# mp3playerLabor_v1.net
KiCad netlist of a schematic drawn in EAGLE
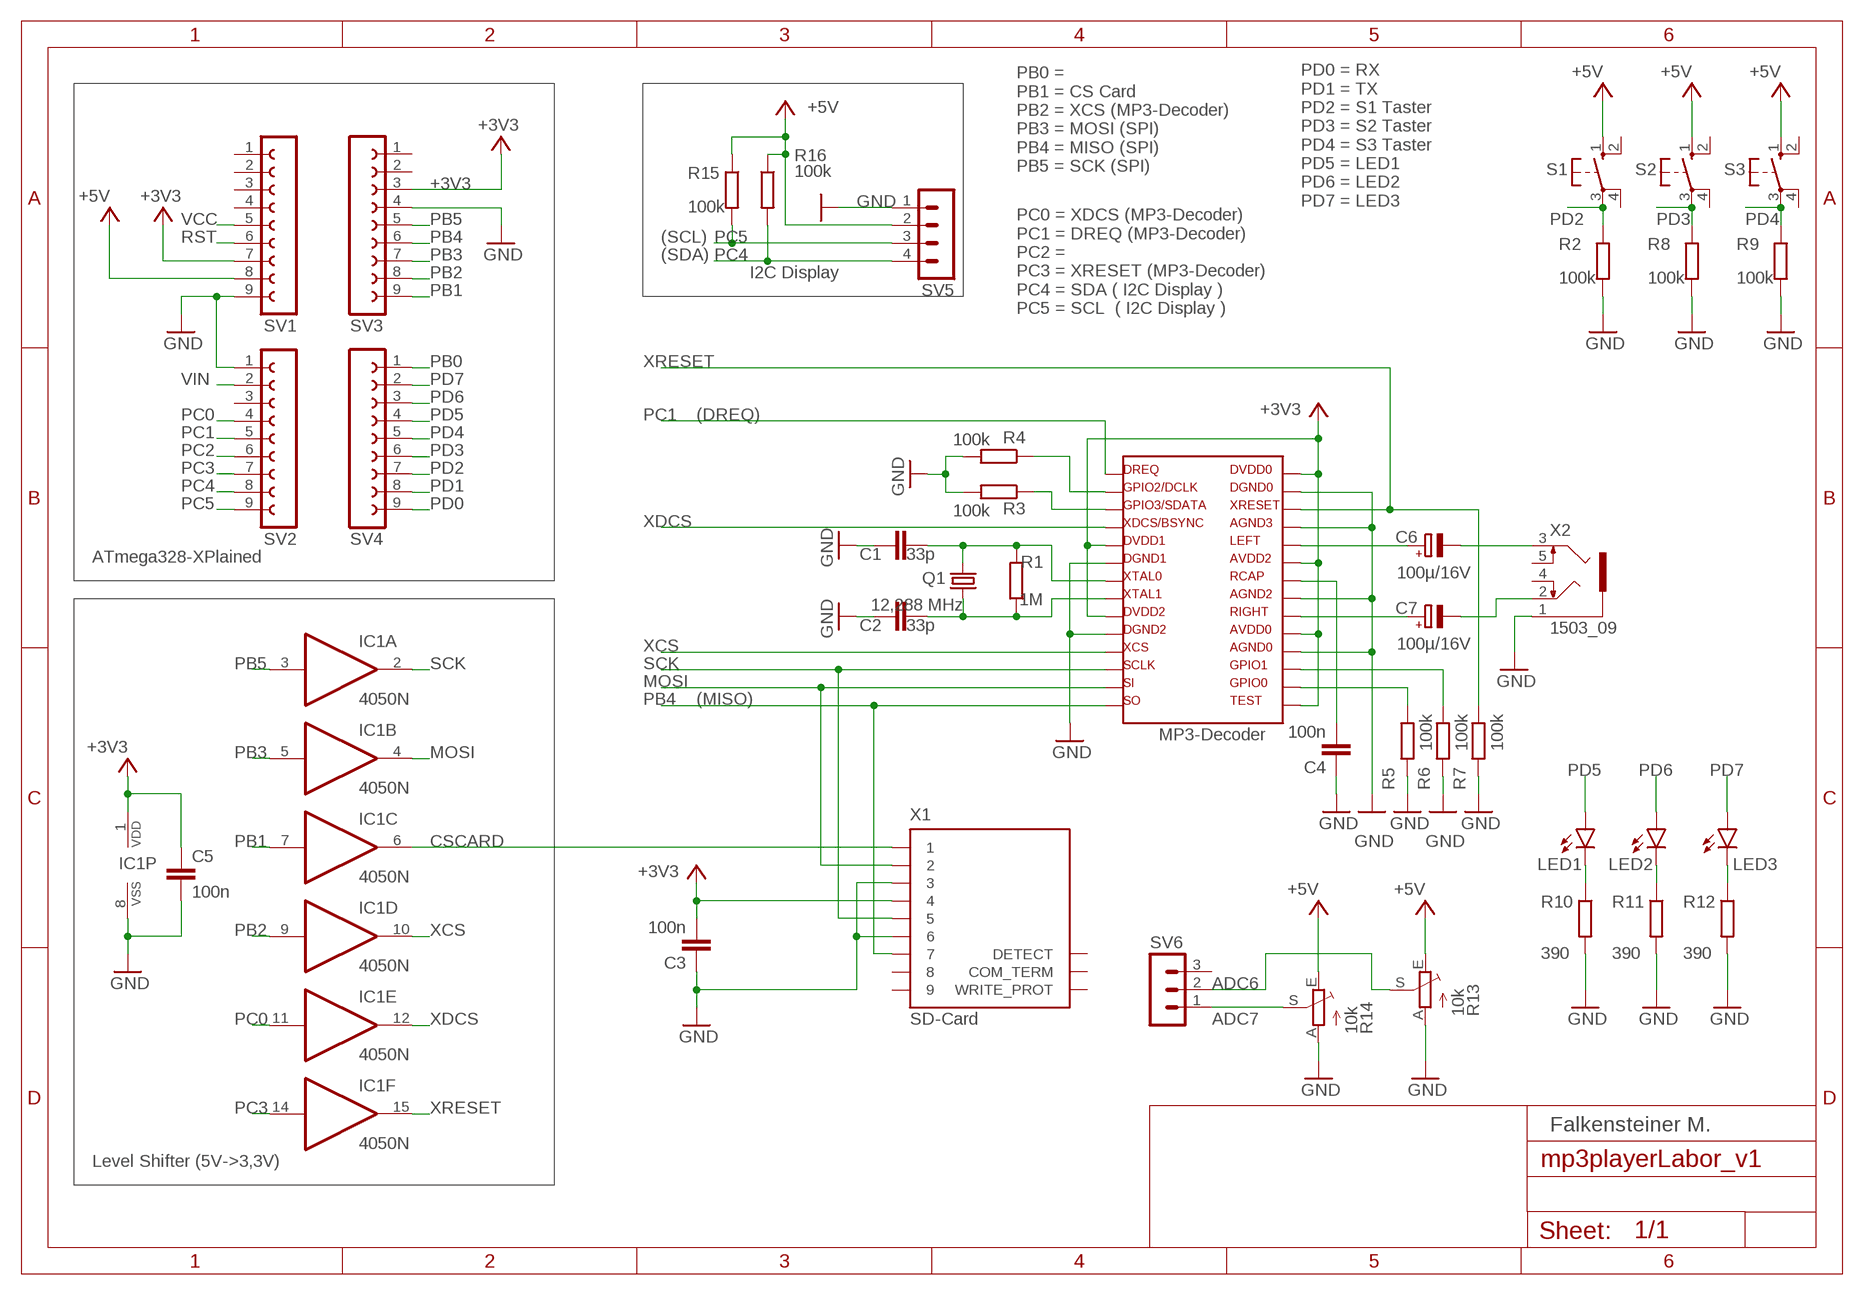
[diagram p0: schematic, sheet 1]

(export (version "E")
  (design (tool "Eeschema 10.0.6"))
  (components
    (comp (ref "C1")
      (value "33p")
      (footprint "eagle-import:C1206K")
      (libsource (lib "eagle-import") (part "C-EUC1206K"))
    )
    (comp (ref "C2")
      (value "33p")
      (footprint "eagle-import:C1206K")
      (libsource (lib "eagle-import") (part "C-EUC1206K"))
    )
    (comp (ref "C3")
      (value "100n")
      (footprint "eagle-import:C1206K")
      (libsource (lib "eagle-import") (part "C-EUC1206K"))
    )
    (comp (ref "C4")
      (value "100n")
      (footprint "eagle-import:C1206K")
      (libsource (lib "eagle-import") (part "C-EUC1206K"))
    )
    (comp (ref "C5")
      (value "100n")
      (footprint "eagle-import:C1206K")
      (libsource (lib "eagle-import") (part "C-EUC1206K"))
    )
    (comp (ref "C6")
      (value "100µ/16V")
      (footprint "eagle-import:UD-6,3X7,7_NICHICON")
      (libsource (lib "eagle-import") (part "CPOL-EUUD-6,3X7,7"))
    )
    (comp (ref "C7")
      (value "100µ/16V")
      (footprint "eagle-import:UD-6,3X7,7_NICHICON")
      (libsource (lib "eagle-import") (part "CPOL-EUUD-6,3X7,7"))
    )
    (comp (ref "IC1")
      (value "4050N")
      (footprint "eagle-import:DIL16")
      (libsource (lib "eagle-import") (part "4050N"))
    )
    (comp (ref "LED1")
      (value "LEDSML1206")
      (footprint "eagle-import:SML1206")
      (libsource (lib "eagle-import") (part "LEDSML1206"))
    )
    (comp (ref "LED2")
      (value "LEDSML1206")
      (footprint "eagle-import:SML1206")
      (libsource (lib "eagle-import") (part "LEDSML1206"))
    )
    (comp (ref "LED3")
      (value "LEDSML1206")
      (footprint "eagle-import:SML1206")
      (libsource (lib "eagle-import") (part "LEDSML1206"))
    )
    (comp (ref "Q1")
      (value "12,288 MHz")
      (footprint "eagle-import:HC49UP")
      (libsource (lib "eagle-import") (part "CRYSTALHC49UP"))
    )
    (comp (ref "R1")
      (value "1M")
      (footprint "eagle-import:R1206")
      (libsource (lib "eagle-import") (part "R-EU_R1206"))
    )
    (comp (ref "R2")
      (value "100k")
      (footprint "eagle-import:R1206")
      (libsource (lib "eagle-import") (part "R-EU_R1206"))
    )
    (comp (ref "R3")
      (value "100k")
      (footprint "eagle-import:R1206")
      (libsource (lib "eagle-import") (part "R-EU_R1206"))
    )
    (comp (ref "R4")
      (value "100k")
      (footprint "eagle-import:R1206")
      (libsource (lib "eagle-import") (part "R-EU_R1206"))
    )
    (comp (ref "R5")
      (value "100k")
      (footprint "eagle-import:R1206")
      (libsource (lib "eagle-import") (part "R-EU_R1206"))
    )
    (comp (ref "R6")
      (value "100k")
      (footprint "eagle-import:R1206")
      (libsource (lib "eagle-import") (part "R-EU_R1206"))
    )
    (comp (ref "R7")
      (value "100k")
      (footprint "eagle-import:R1206")
      (libsource (lib "eagle-import") (part "R-EU_R1206"))
    )
    (comp (ref "R8")
      (value "100k")
      (footprint "eagle-import:R1206")
      (libsource (lib "eagle-import") (part "R-EU_R1206"))
    )
    (comp (ref "R9")
      (value "100k")
      (footprint "eagle-import:R1206")
      (libsource (lib "eagle-import") (part "R-EU_R1206"))
    )
    (comp (ref "R10")
      (value "390")
      (footprint "eagle-import:R1206")
      (libsource (lib "eagle-import") (part "R-EU_R1206"))
    )
    (comp (ref "R11")
      (value "390")
      (footprint "eagle-import:R1206")
      (libsource (lib "eagle-import") (part "R-EU_R1206"))
    )
    (comp (ref "R12")
      (value "390")
      (footprint "eagle-import:R1206")
      (libsource (lib "eagle-import") (part "R-EU_R1206"))
    )
    (comp (ref "R13")
      (value "10k")
      (footprint "eagle-import:CA6V")
      (libsource (lib "eagle-import") (part "TRIM_EU-CA6V"))
    )
    (comp (ref "R14")
      (value "10k")
      (footprint "eagle-import:CA6V")
      (libsource (lib "eagle-import") (part "TRIM_EU-CA6V"))
    )
    (comp (ref "R15")
      (value "100k")
      (footprint "eagle-import:R1206")
      (libsource (lib "eagle-import") (part "R-EU_R1206"))
    )
    (comp (ref "R16")
      (value "100k")
      (footprint "eagle-import:R1206")
      (libsource (lib "eagle-import") (part "R-EU_R1206"))
    )
    (comp (ref "S1")
      (value "10-XX")
      (footprint "eagle-import:B3F-10XX")
      (libsource (lib "eagle-import") (part "10-XX"))
    )
    (comp (ref "S2")
      (value "10-XX")
      (footprint "eagle-import:B3F-10XX")
      (libsource (lib "eagle-import") (part "10-XX"))
    )
    (comp (ref "S3")
      (value "10-XX")
      (footprint "eagle-import:B3F-10XX")
      (libsource (lib "eagle-import") (part "10-XX"))
    )
    (comp (ref "SV1")
      (value "FE09-1")
      (footprint "eagle-import:FE09")
      (libsource (lib "eagle-import") (part "FE09-1"))
    )
    (comp (ref "SV2")
      (value "FE09-1")
      (footprint "eagle-import:FE09")
      (libsource (lib "eagle-import") (part "FE09-1"))
    )
    (comp (ref "SV3")
      (value "FE09-1")
      (footprint "eagle-import:FE09")
      (libsource (lib "eagle-import") (part "FE09-1"))
    )
    (comp (ref "SV4")
      (value "FE09-1")
      (footprint "eagle-import:FE09")
      (libsource (lib "eagle-import") (part "FE09-1"))
    )
    (comp (ref "SV5")
      (value "MA04-1")
      (footprint "eagle-import:MA04-1")
      (libsource (lib "eagle-import") (part "MA04-1"))
    )
    (comp (ref "SV6")
      (value "MA03-1")
      (footprint "eagle-import:MA03-1")
      (libsource (lib "eagle-import") (part "MA03-1"))
    )
    (comp (ref "U$1")
      (value "VS1011")
      (footprint "eagle-import:SOIC-28")
      (libsource (lib "eagle-import") (part "VS1011"))
    )
    (comp (ref "X1")
      (value "SD-Card")
      (footprint "eagle-import:FPS009-3000")
      (libsource (lib "eagle-import") (part "FPS009-3000"))
    )
    (comp (ref "X2")
      (value "1503_09")
      (footprint "eagle-import:1503_09")
      (libsource (lib "eagle-import") (part "1503_09"))
    )
  )
  (nets
    (net (code "1") (name "+3V3") (class "Default")
      (node (ref "C3") (pin "2") (pinfunction "2_2") (pintype "passive"))
      (node (ref "C5") (pin "1") (pinfunction "1_1") (pintype "passive"))
      (node (ref "IC1") (pin "1") (pinfunction "VDD_1") (pintype "power_in"))
      (node (ref "SV1") (pin "7") (pinfunction "7_7") (pintype "passive"))
      (node (ref "SV3") (pin "3") (pinfunction "3_3") (pintype "passive"))
      (node (ref "U$1") (pin "15") (pinfunction "P$15_15") (pintype "bidirectional"))
      (node (ref "U$1") (pin "19") (pinfunction "P$19_19") (pintype "bidirectional"))
      (node (ref "U$1") (pin "23") (pinfunction "P$23_23") (pintype "bidirectional"))
      (node (ref "U$1") (pin "28") (pinfunction "P$28_28") (pintype "bidirectional"))
      (node (ref "U$1") (pin "5") (pinfunction "P$5_5") (pintype "bidirectional"))
      (node (ref "U$1") (pin "9") (pinfunction "P$9_9") (pintype "bidirectional"))
      (node (ref "X1") (pin "4") (pinfunction "4_4") (pintype "input"))
    )
    (net (code "2") (name "+5V") (class "Default")
      (node (ref "R13") (pin "E") (pinfunction "E_E") (pintype "passive"))
      (node (ref "R14") (pin "E") (pinfunction "E_E") (pintype "passive"))
      (node (ref "R15") (pin "1") (pinfunction "1_1") (pintype "passive"))
      (node (ref "R16") (pin "1") (pinfunction "1_1") (pintype "passive"))
      (node (ref "S1") (pin "1") (pinfunction "S_1") (pintype "passive"))
      (node (ref "S2") (pin "1") (pinfunction "S_1") (pintype "passive"))
      (node (ref "S3") (pin "1") (pinfunction "S_1") (pintype "passive"))
      (node (ref "SV1") (pin "8") (pinfunction "8_8") (pintype "passive"))
      (node (ref "SV5") (pin "2") (pinfunction "2_2") (pintype "passive"))
    )
    (net (code "3") (name "/ADC6") (class "Default")
      (node (ref "R13") (pin "S") (pinfunction "S_S") (pintype "passive"))
      (node (ref "SV6") (pin "2") (pinfunction "2_2") (pintype "passive"))
    )
    (net (code "4") (name "/ADC7") (class "Default")
      (node (ref "R14") (pin "S") (pinfunction "S_S") (pintype "passive"))
      (node (ref "SV6") (pin "1") (pinfunction "1_1") (pintype "passive"))
    )
    (net (code "5") (name "/CSCARD") (class "Default")
      (node (ref "IC1") (pin "6") (pinfunction "O_6") (pintype "output"))
      (node (ref "X1") (pin "1") (pinfunction "1_1") (pintype "input"))
    )
    (net (code "6") (name "/MOSI") (class "Default")
      (node (ref "IC1") (pin "4") (pinfunction "O_4") (pintype "output"))
      (node (ref "U$1") (pin "13") (pinfunction "P$13_13") (pintype "bidirectional"))
      (node (ref "X1") (pin "2") (pinfunction "2_2") (pintype "input"))
    )
    (net (code "7") (name "/PB0") (class "Default")
      (node (ref "SV4") (pin "1") (pinfunction "1_1") (pintype "passive"))
    )
    (net (code "8") (name "/PB1") (class "Default")
      (node (ref "IC1") (pin "7") (pinfunction "I_7") (pintype "input"))
      (node (ref "SV3") (pin "9") (pinfunction "9_9") (pintype "passive"))
    )
    (net (code "9") (name "/PB2") (class "Default")
      (node (ref "IC1") (pin "9") (pinfunction "I_9") (pintype "input"))
      (node (ref "SV3") (pin "8") (pinfunction "8_8") (pintype "passive"))
    )
    (net (code "10") (name "/PB3") (class "Default")
      (node (ref "IC1") (pin "5") (pinfunction "I_5") (pintype "input"))
      (node (ref "SV3") (pin "7") (pinfunction "7_7") (pintype "passive"))
    )
    (net (code "11") (name "/PB4") (class "Default")
      (node (ref "SV3") (pin "6") (pinfunction "6_6") (pintype "passive"))
      (node (ref "U$1") (pin "14") (pinfunction "P$14_14") (pintype "bidirectional"))
      (node (ref "X1") (pin "7") (pinfunction "7_7") (pintype "input"))
    )
    (net (code "12") (name "/PB5") (class "Default")
      (node (ref "IC1") (pin "3") (pinfunction "I_3") (pintype "input"))
      (node (ref "SV3") (pin "5") (pinfunction "5_5") (pintype "passive"))
    )
    (net (code "13") (name "/PC0") (class "Default")
      (node (ref "IC1") (pin "11") (pinfunction "I_11") (pintype "input"))
      (node (ref "SV2") (pin "4") (pinfunction "4_4") (pintype "passive"))
    )
    (net (code "14") (name "/PC1") (class "Default")
      (node (ref "SV2") (pin "5") (pinfunction "5_5") (pintype "passive"))
      (node (ref "U$1") (pin "1") (pinfunction "P$1_1") (pintype "bidirectional"))
    )
    (net (code "15") (name "/PC2") (class "Default")
      (node (ref "SV2") (pin "6") (pinfunction "6_6") (pintype "passive"))
    )
    (net (code "16") (name "/PC3") (class "Default")
      (node (ref "IC1") (pin "14") (pinfunction "I_14") (pintype "input"))
      (node (ref "SV2") (pin "7") (pinfunction "7_7") (pintype "passive"))
    )
    (net (code "17") (name "/PC4") (class "Default")
      (node (ref "R16") (pin "2") (pinfunction "2_2") (pintype "passive"))
      (node (ref "SV2") (pin "8") (pinfunction "8_8") (pintype "passive"))
      (node (ref "SV5") (pin "4") (pinfunction "4_4") (pintype "passive"))
    )
    (net (code "18") (name "/PC5") (class "Default")
      (node (ref "R15") (pin "2") (pinfunction "2_2") (pintype "passive"))
      (node (ref "SV2") (pin "9") (pinfunction "9_9") (pintype "passive"))
      (node (ref "SV5") (pin "3") (pinfunction "3_3") (pintype "passive"))
    )
    (net (code "19") (name "/PD0") (class "Default")
      (node (ref "SV4") (pin "9") (pinfunction "9_9") (pintype "passive"))
    )
    (net (code "20") (name "/PD1") (class "Default")
      (node (ref "SV4") (pin "8") (pinfunction "8_8") (pintype "passive"))
    )
    (net (code "21") (name "/PD2") (class "Default")
      (node (ref "R2") (pin "1") (pinfunction "1_1") (pintype "passive"))
      (node (ref "S1") (pin "3") (pinfunction "P_3") (pintype "passive"))
      (node (ref "SV4") (pin "7") (pinfunction "7_7") (pintype "passive"))
    )
    (net (code "22") (name "/PD3") (class "Default")
      (node (ref "R8") (pin "1") (pinfunction "1_1") (pintype "passive"))
      (node (ref "S2") (pin "3") (pinfunction "P_3") (pintype "passive"))
      (node (ref "SV4") (pin "6") (pinfunction "6_6") (pintype "passive"))
    )
    (net (code "23") (name "/PD4") (class "Default")
      (node (ref "R9") (pin "1") (pinfunction "1_1") (pintype "passive"))
      (node (ref "S3") (pin "3") (pinfunction "P_3") (pintype "passive"))
      (node (ref "SV4") (pin "5") (pinfunction "5_5") (pintype "passive"))
    )
    (net (code "24") (name "/PD5") (class "Default")
      (node (ref "LED1") (pin "A") (pinfunction "A_A") (pintype "passive"))
      (node (ref "SV4") (pin "4") (pinfunction "4_4") (pintype "passive"))
    )
    (net (code "25") (name "/PD6") (class "Default")
      (node (ref "LED2") (pin "A") (pinfunction "A_A") (pintype "passive"))
      (node (ref "SV4") (pin "3") (pinfunction "3_3") (pintype "passive"))
    )
    (net (code "26") (name "/PD7") (class "Default")
      (node (ref "LED3") (pin "A") (pinfunction "A_A") (pintype "passive"))
      (node (ref "SV4") (pin "2") (pinfunction "2_2") (pintype "passive"))
    )
    (net (code "27") (name "/RST") (class "Default")
      (node (ref "SV1") (pin "6") (pinfunction "6_6") (pintype "passive"))
    )
    (net (code "28") (name "/SCK") (class "Default")
      (node (ref "IC1") (pin "2") (pinfunction "O_2") (pintype "output"))
      (node (ref "U$1") (pin "12") (pinfunction "P$12_12") (pintype "bidirectional"))
      (node (ref "X1") (pin "5") (pinfunction "5_5") (pintype "input"))
    )
    (net (code "29") (name "/VCC") (class "Default")
      (node (ref "SV1") (pin "5") (pinfunction "5_5") (pintype "passive"))
    )
    (net (code "30") (name "/VIN") (class "Default")
      (node (ref "SV2") (pin "2") (pinfunction "2_2") (pintype "passive"))
    )
    (net (code "31") (name "/XCS") (class "Default")
      (node (ref "IC1") (pin "10") (pinfunction "O_10") (pintype "output"))
      (node (ref "U$1") (pin "11") (pinfunction "P$11_11") (pintype "bidirectional"))
    )
    (net (code "32") (name "/XDCS") (class "Default")
      (node (ref "IC1") (pin "12") (pinfunction "O_12") (pintype "output"))
      (node (ref "U$1") (pin "4") (pinfunction "P$4_4") (pintype "bidirectional"))
    )
    (net (code "33") (name "/XRESET") (class "Default")
      (node (ref "IC1") (pin "15") (pinfunction "O_15") (pintype "output"))
      (node (ref "R7") (pin "1") (pinfunction "1_1") (pintype "passive"))
      (node (ref "U$1") (pin "26") (pinfunction "P$26_26") (pintype "bidirectional"))
    )
    (net (code "34") (name "GND") (class "Default")
      (node (ref "C1") (pin "1") (pinfunction "1_1") (pintype "passive"))
      (node (ref "C2") (pin "1") (pinfunction "1_1") (pintype "passive"))
      (node (ref "C3") (pin "1") (pinfunction "1_1") (pintype "passive"))
      (node (ref "C4") (pin "1") (pinfunction "1_1") (pintype "passive"))
      (node (ref "C5") (pin "2") (pinfunction "2_2") (pintype "passive"))
      (node (ref "IC1") (pin "8") (pinfunction "VSS_8") (pintype "power_in"))
      (node (ref "R10") (pin "2") (pinfunction "2_2") (pintype "passive"))
      (node (ref "R11") (pin "2") (pinfunction "2_2") (pintype "passive"))
      (node (ref "R12") (pin "2") (pinfunction "2_2") (pintype "passive"))
      (node (ref "R13") (pin "A") (pinfunction "A_A") (pintype "passive"))
      (node (ref "R14") (pin "A") (pinfunction "A_A") (pintype "passive"))
      (node (ref "R2") (pin "2") (pinfunction "2_2") (pintype "passive"))
      (node (ref "R3") (pin "2") (pinfunction "2_2") (pintype "passive"))
      (node (ref "R4") (pin "2") (pinfunction "2_2") (pintype "passive"))
      (node (ref "R5") (pin "2") (pinfunction "2_2") (pintype "passive"))
      (node (ref "R6") (pin "2") (pinfunction "2_2") (pintype "passive"))
      (node (ref "R7") (pin "2") (pinfunction "2_2") (pintype "passive"))
      (node (ref "R8") (pin "2") (pinfunction "2_2") (pintype "passive"))
      (node (ref "R9") (pin "2") (pinfunction "2_2") (pintype "passive"))
      (node (ref "SV1") (pin "9") (pinfunction "9_9") (pintype "passive"))
      (node (ref "SV2") (pin "1") (pinfunction "1_1") (pintype "passive"))
      (node (ref "SV3") (pin "4") (pinfunction "4_4") (pintype "passive"))
      (node (ref "SV5") (pin "1") (pinfunction "1_1") (pintype "passive"))
      (node (ref "U$1") (pin "10") (pinfunction "P$10_10") (pintype "bidirectional"))
      (node (ref "U$1") (pin "18") (pinfunction "P$18_18") (pintype "bidirectional"))
      (node (ref "U$1") (pin "21") (pinfunction "P$21_21") (pintype "bidirectional"))
      (node (ref "U$1") (pin "25") (pinfunction "P$25_25") (pintype "bidirectional"))
      (node (ref "U$1") (pin "27") (pinfunction "P$27_27") (pintype "bidirectional"))
      (node (ref "U$1") (pin "6") (pinfunction "P$6_6") (pintype "bidirectional"))
      (node (ref "X1") (pin "3") (pinfunction "3_3") (pintype "input"))
      (node (ref "X1") (pin "6") (pinfunction "6_6") (pintype "input"))
      (node (ref "X2") (pin "1") (pinfunction "1_1") (pintype "passive"))
    )
    (net (code "35") (name "Net-(C6-Pad-)") (class "Default")
      (node (ref "C6") (pin "-") (pinfunction "-_-") (pintype "passive"))
      (node (ref "X2") (pin "3") (pinfunction "3_3") (pintype "passive"))
    )
    (net (code "36") (name "Net-(C7-Pad-)") (class "Default")
      (node (ref "C7") (pin "-") (pinfunction "-_-") (pintype "passive"))
      (node (ref "X2") (pin "2") (pinfunction "2_2") (pintype "passive"))
    )
    (net (code "37") (name "Net-(LED1-PadC)") (class "Default")
      (node (ref "LED1") (pin "C") (pinfunction "C_C") (pintype "passive"))
      (node (ref "R10") (pin "1") (pinfunction "1_1") (pintype "passive"))
    )
    (net (code "38") (name "Net-(LED2-PadC)") (class "Default")
      (node (ref "LED2") (pin "C") (pinfunction "C_C") (pintype "passive"))
      (node (ref "R11") (pin "1") (pinfunction "1_1") (pintype "passive"))
    )
    (net (code "39") (name "Net-(LED3-PadC)") (class "Default")
      (node (ref "LED3") (pin "C") (pinfunction "C_C") (pintype "passive"))
      (node (ref "R12") (pin "1") (pinfunction "1_1") (pintype "passive"))
    )
    (net (code "40") (name "Net-(U$1-P$2)") (class "Default")
      (node (ref "R4") (pin "1") (pinfunction "1_1") (pintype "passive"))
      (node (ref "U$1") (pin "2") (pinfunction "P$2_2") (pintype "bidirectional"))
    )
    (net (code "41") (name "Net-(U$1-P$3)") (class "Default")
      (node (ref "R3") (pin "1") (pinfunction "1_1") (pintype "passive"))
      (node (ref "U$1") (pin "3") (pinfunction "P$3_3") (pintype "bidirectional"))
    )
    (net (code "42") (name "Net-(U$1-P$7)") (class "Default")
      (node (ref "C1") (pin "2") (pinfunction "2_2") (pintype "passive"))
      (node (ref "Q1") (pin "2") (pinfunction "2_2") (pintype "passive"))
      (node (ref "R1") (pin "2") (pinfunction "2_2") (pintype "passive"))
      (node (ref "U$1") (pin "7") (pinfunction "P$7_7") (pintype "bidirectional"))
    )
    (net (code "43") (name "Net-(U$1-P$8)") (class "Default")
      (node (ref "C2") (pin "2") (pinfunction "2_2") (pintype "passive"))
      (node (ref "Q1") (pin "1") (pinfunction "1_1") (pintype "passive"))
      (node (ref "R1") (pin "1") (pinfunction "1_1") (pintype "passive"))
      (node (ref "U$1") (pin "8") (pinfunction "P$8_8") (pintype "bidirectional"))
    )
    (net (code "44") (name "Net-(U$1-P$16)") (class "Default")
      (node (ref "R5") (pin "1") (pinfunction "1_1") (pintype "passive"))
      (node (ref "U$1") (pin "16") (pinfunction "P$16_16") (pintype "bidirectional"))
    )
    (net (code "45") (name "Net-(U$1-P$17)") (class "Default")
      (node (ref "R6") (pin "1") (pinfunction "1_1") (pintype "passive"))
      (node (ref "U$1") (pin "17") (pinfunction "P$17_17") (pintype "bidirectional"))
    )
    (net (code "46") (name "Net-(U$1-P$20)") (class "Default")
      (node (ref "C7") (pin "+") (pinfunction "+_+") (pintype "passive"))
      (node (ref "U$1") (pin "20") (pinfunction "P$20_20") (pintype "bidirectional"))
    )
    (net (code "47") (name "Net-(U$1-P$22)") (class "Default")
      (node (ref "C4") (pin "2") (pinfunction "2_2") (pintype "passive"))
      (node (ref "U$1") (pin "22") (pinfunction "P$22_22") (pintype "bidirectional"))
    )
    (net (code "48") (name "Net-(U$1-P$24)") (class "Default")
      (node (ref "C6") (pin "+") (pinfunction "+_+") (pintype "passive"))
      (node (ref "U$1") (pin "24") (pinfunction "P$24_24") (pintype "bidirectional"))
    )
    (net (code "49") (name "unconnected-(S1-P1-Pad4)") (class "Default")
      (node (ref "S1") (pin "4") (pinfunction "P1_4") (pintype "passive"))
    )
    (net (code "50") (name "unconnected-(S1-S1-Pad2)") (class "Default")
      (node (ref "S1") (pin "2") (pinfunction "S1_2") (pintype "passive"))
    )
    (net (code "51") (name "unconnected-(S2-P1-Pad4)") (class "Default")
      (node (ref "S2") (pin "4") (pinfunction "P1_4") (pintype "passive"))
    )
    (net (code "52") (name "unconnected-(S2-S1-Pad2)") (class "Default")
      (node (ref "S2") (pin "2") (pinfunction "S1_2") (pintype "passive"))
    )
    (net (code "53") (name "unconnected-(S3-P1-Pad4)") (class "Default")
      (node (ref "S3") (pin "4") (pinfunction "P1_4") (pintype "passive"))
    )
    (net (code "54") (name "unconnected-(S3-S1-Pad2)") (class "Default")
      (node (ref "S3") (pin "2") (pinfunction "S1_2") (pintype "passive"))
    )
    (net (code "55") (name "unconnected-(SV1-Pad1)") (class "Default")
      (node (ref "SV1") (pin "1") (pinfunction "1_1") (pintype "passive"))
    )
    (net (code "56") (name "unconnected-(SV1-Pad2)") (class "Default")
      (node (ref "SV1") (pin "2") (pinfunction "2_2") (pintype "passive"))
    )
    (net (code "57") (name "unconnected-(SV1-Pad3)") (class "Default")
      (node (ref "SV1") (pin "3") (pinfunction "3_3") (pintype "passive"))
    )
    (net (code "58") (name "unconnected-(SV1-Pad4)") (class "Default")
      (node (ref "SV1") (pin "4") (pinfunction "4_4") (pintype "passive"))
    )
    (net (code "59") (name "unconnected-(SV2-Pad3)") (class "Default")
      (node (ref "SV2") (pin "3") (pinfunction "3_3") (pintype "passive"))
    )
    (net (code "60") (name "unconnected-(SV3-Pad1)") (class "Default")
      (node (ref "SV3") (pin "1") (pinfunction "1_1") (pintype "passive"))
    )
    (net (code "61") (name "unconnected-(SV3-Pad2)") (class "Default")
      (node (ref "SV3") (pin "2") (pinfunction "2_2") (pintype "passive"))
    )
    (net (code "62") (name "unconnected-(SV6-Pad3)") (class "Default")
      (node (ref "SV6") (pin "3") (pinfunction "3_3") (pintype "passive"))
    )
    (net (code "63") (name "unconnected-(X1-Pad8)") (class "Default")
      (node (ref "X1") (pin "8") (pinfunction "8_8") (pintype "input"))
    )
    (net (code "64") (name "unconnected-(X1-Pad9)") (class "Default")
      (node (ref "X1") (pin "9") (pinfunction "9_9") (pintype "input"))
    )
    (net (code "65") (name "unconnected-(X1-PadCOM_TERM)") (class "Default")
      (node (ref "X1") (pin "COM_TERM") (pinfunction "COM_TERM_COM_TERM") (pintype "input"))
    )
    (net (code "66") (name "unconnected-(X1-PadDETECT)") (class "Default")
      (node (ref "X1") (pin "DETECT") (pinfunction "DETECT_DETECT") (pintype "input"))
    )
    (net (code "67") (name "unconnected-(X1-PadWRITE_PROT)") (class "Default")
      (node (ref "X1") (pin "WRITE_PROT") (pinfunction "WRITE_PROT_WRITE_PROT") (pintype "input"))
    )
    (net (code "68") (name "unconnected-(X2-Pad4)") (class "Default")
      (node (ref "X2") (pin "4") (pinfunction "4_4") (pintype "passive"))
    )
    (net (code "69") (name "unconnected-(X2-Pad5)") (class "Default")
      (node (ref "X2") (pin "5") (pinfunction "5_5") (pintype "passive"))
    )
  )
)
